# ProDocument_PWRTool_500_2024-05-11.net
KiCad netlist of a schematic drawn in EasyEDA Pro
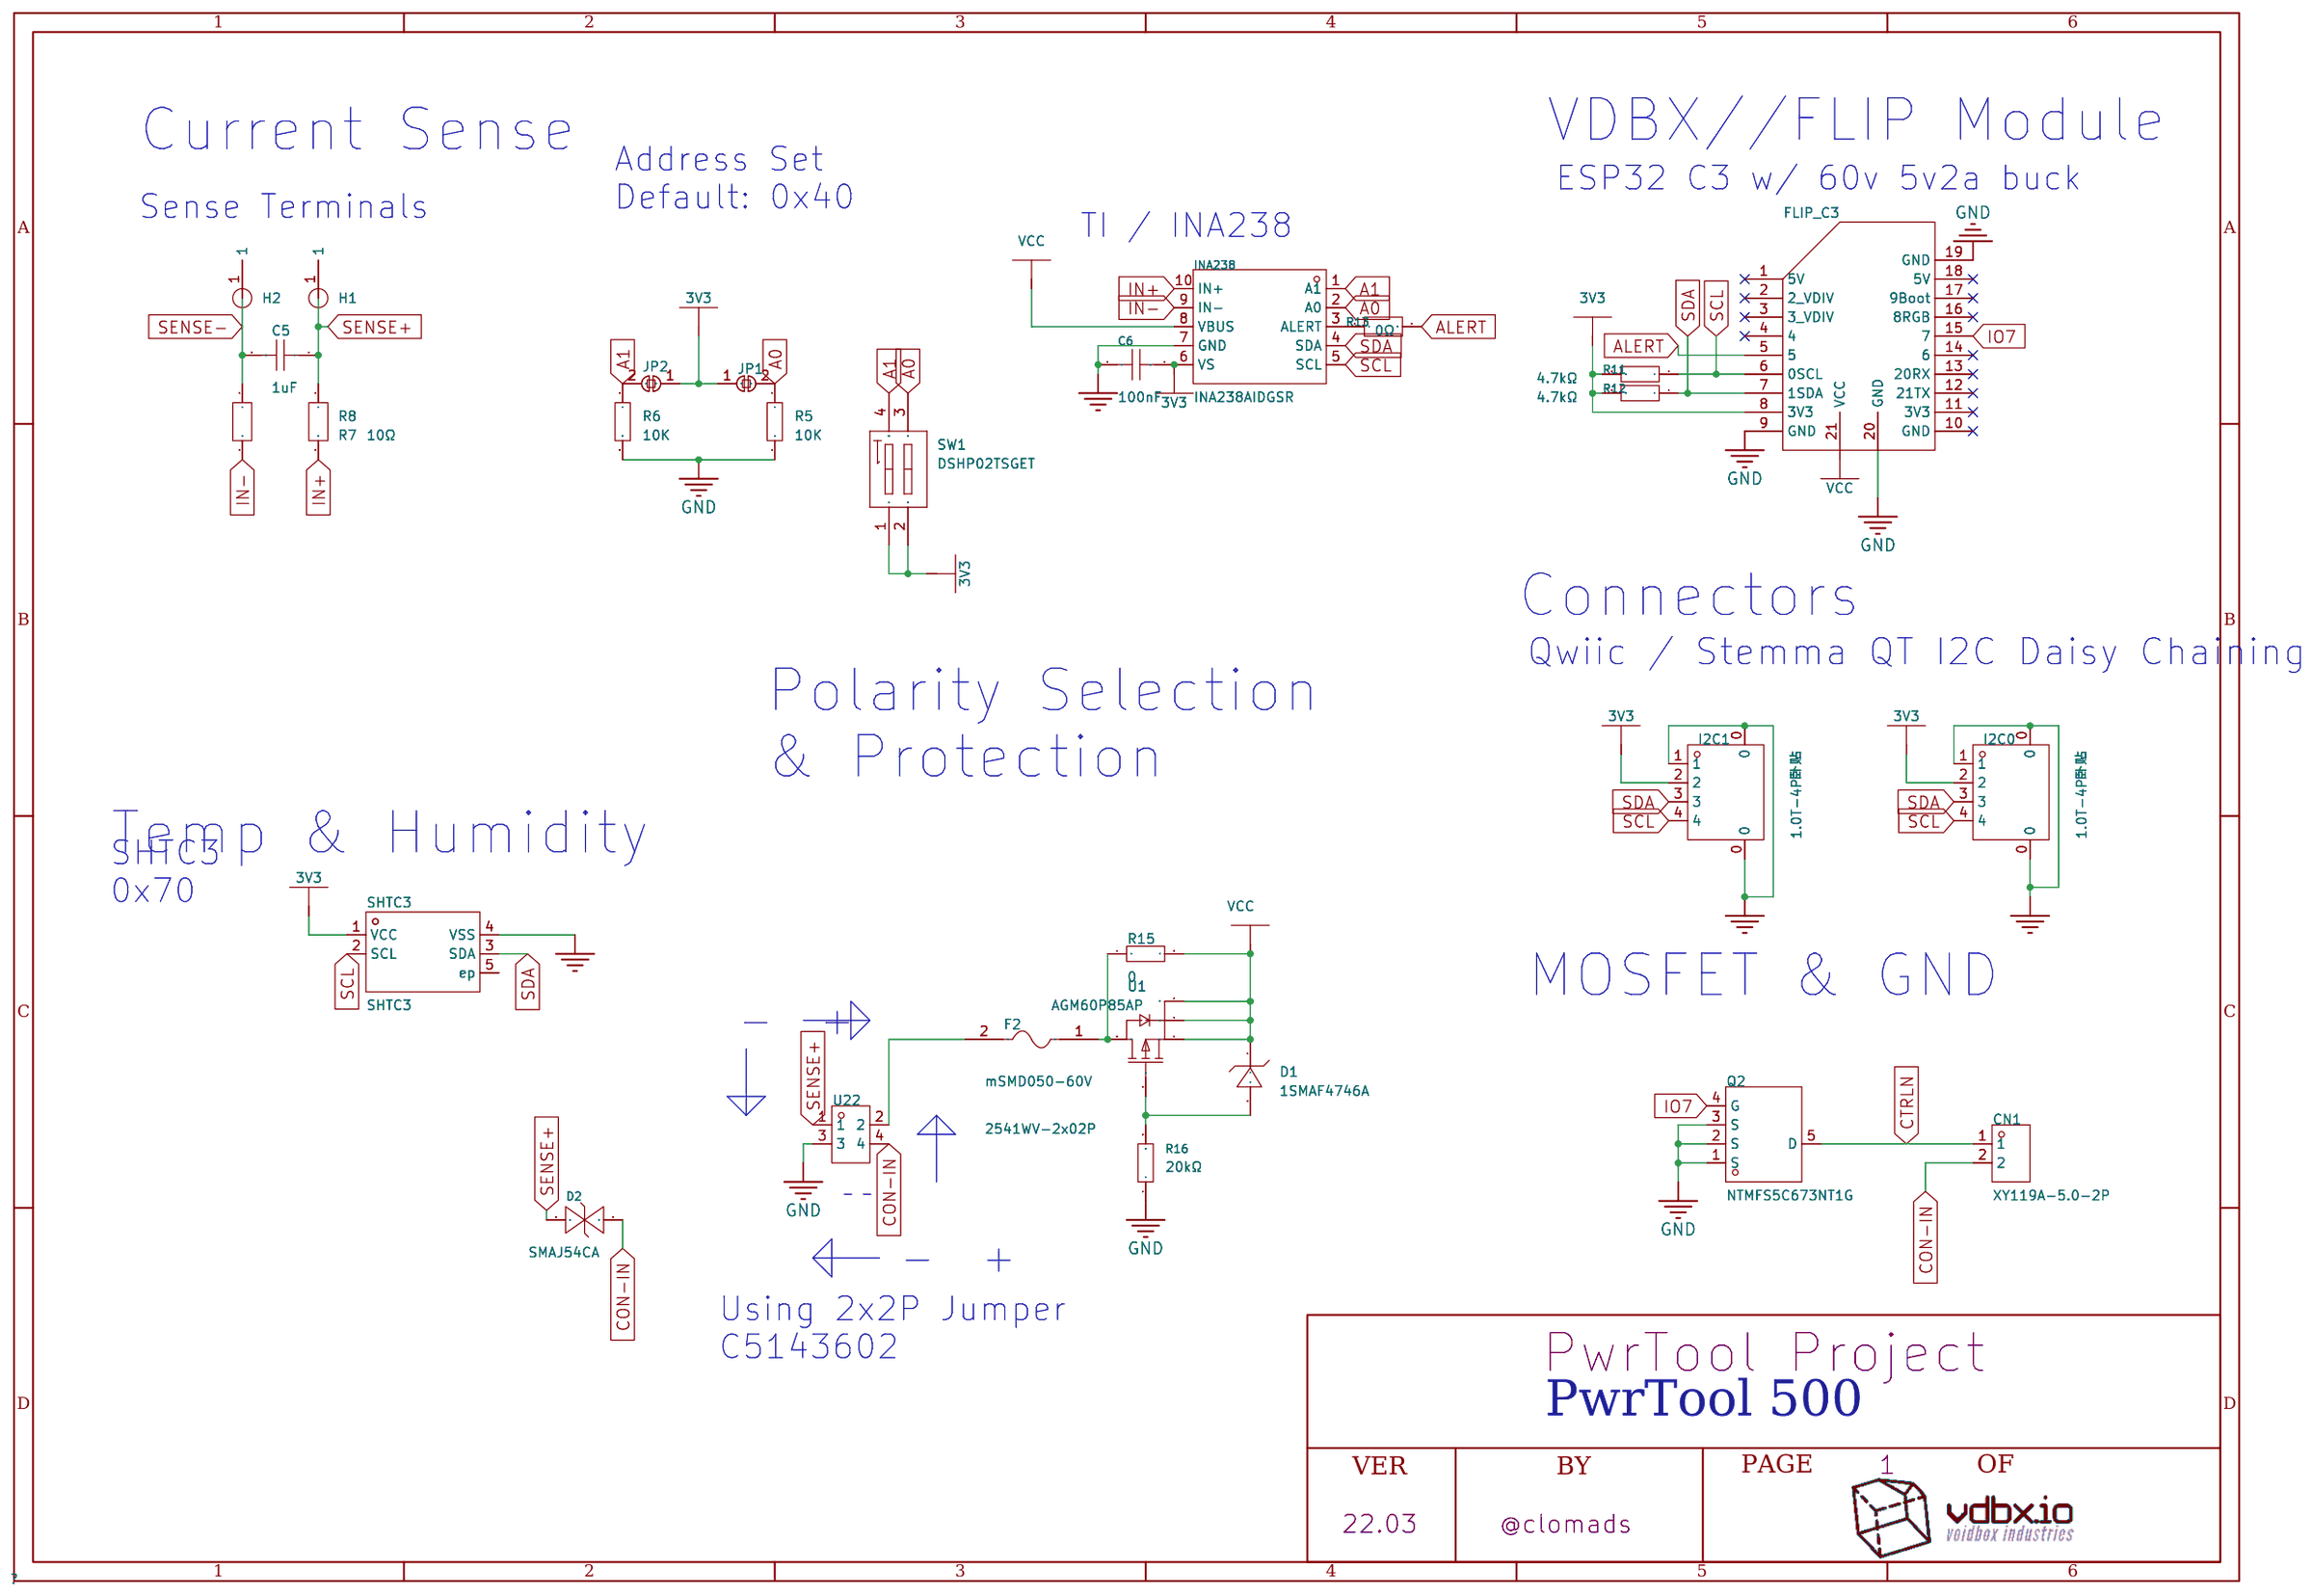
[diagram p0: schematic sheet]

(export (version "E")
  (design (tool "Eeschema 10.0.6"))
  (components
    (comp (ref "C5")
      (value "1uF")
      (footprint "easyedapro:C1206")
      (fields
        (field (name "Manufacturer Part") "TCC1206X7R105K101HT")
        (field (name "Manufacturer") "CCTC(三环)")
      )
      (libsource (lib "easyedapro") (part "TCC1206X7R105K101HT"))
    )
    (comp (ref "C6")
      (value "100nF")
      (footprint "easyedapro:C0402")
      (fields
        (field (name "Manufacturer Part") "CC0402JRX7R6BB104")
        (field (name "Manufacturer") "YAGEO(国巨)")
      )
      (libsource (lib "easyedapro") (part "CC0402JRX7R6BB104"))
    )
    (comp (ref "CN1")
      (value "XY119A-5.0-2P")
      (footprint "easyedapro:CONN-TH_XY119A-5.0-2P")
      (fields (field (name "Manufacturer") "XINLAIYA(新莱亚)"))
      (libsource (lib "easyedapro") (part "XY119A-5.0-2P"))
    )
    (comp (ref "D1")
      (value "1SMAF4746A")
      (footprint "easyedapro:SMAF_L3.5-W2.6-LS4.7-RD")
      (fields (field (name "Manufacturer") "晶导微电子"))
      (libsource (lib "easyedapro") (part "1SMAF4746A"))
    )
    (comp (ref "D2")
      (value "SMAJ54CA")
      (footprint "easyedapro:SMA_L4.4-W2.6-LS5.0-BI")
      (fields (field (name "Manufacturer") "TWGMC(台湾迪嘉)"))
      (libsource (lib "easyedapro") (part "SMAJ54CA_C726801"))
    )
    (comp (ref "F2")
      (value "mSMD050-60V")
      (footprint "easyedapro:F1812")
      (description "Operating Voltage (Max):60V Hold Current:500mA Current Rating (Max):100A Trip Current:1A")
      (fields (field (name "Manufacturer") "台湾陆海"))
      (libsource (lib "easyedapro") (part "mSMD050-60V"))
    )
    (comp (ref "FLIP_C3")
      (value "~")
      (footprint "easyedapro:VDBX//FLIP")
      (description "2.54mm DIP header for VDBX//FLIP")
      (libsource (lib "easyedapro") (part "VDBX//FLIP"))
    )
    (comp (ref "H1")
      (value "M2.5x3")
      (footprint "easyedapro:HDMod_MountingHole:SMTSO2530CTJ")
      (libsource (lib "easyedapro") (part "Mechanical Mount Hole 3mm"))
    )
    (comp (ref "H2")
      (value "M2.5x3")
      (footprint "easyedapro:HDMod_MountingHole:SMTSO2530CTJ")
      (libsource (lib "easyedapro") (part "Mechanical Mount Hole 3mm"))
    )
    (comp (ref "I2C0")
      (value "1.0T-4P卧贴")
      (footprint "easyedapro:CONN-SMD_1.0T-4P")
      (fields (field (name "Manufacturer") "BOOMELE(博穆精密)"))
      (libsource (lib "easyedapro") (part "1.0T-4P_C145956"))
    )
    (comp (ref "I2C1")
      (value "1.0T-4P卧贴")
      (footprint "easyedapro:CONN-SMD_1.0T-4P")
      (fields (field (name "Manufacturer") "BOOMELE(博穆精密)"))
      (libsource (lib "easyedapro") (part "1.0T-4P_C145956"))
    )
    (comp (ref "INA238")
      (value "INA238AIDGSR")
      (footprint "easyedapro:VSSOP-10_L3.0-W3.0-P0.50-LS4.9-BL")
      (fields (field (name "Manufacturer") "TI(德州仪器)"))
      (libsource (lib "easyedapro") (part "INA238AIDGSR"))
    )
    (comp (ref "JP1")
      (value "Jumper_SolderJumper_2_Bridged")
      (footprint "easyedapro:JUMPER")
      (libsource (lib "easyedapro") (part "Jumper_SolderJumper_2_Bridged"))
    )
    (comp (ref "JP2")
      (value "Jumper_SolderJumper_2_Bridged")
      (footprint "easyedapro:JUMPER")
      (libsource (lib "easyedapro") (part "Jumper_SolderJumper_2_Bridged"))
    )
    (comp (ref "Q2")
      (value "NTMFS5C673NT1G")
      (footprint "easyedapro:DFN-5_L4.9-W5.9-P1.27-LS6.2-BL")
      (fields (field (name "Manufacturer") "onsemi(安森美)"))
      (libsource (lib "easyedapro") (part "NTMFS5C673NT1G"))
    )
    (comp (ref "R5") (value "10K") (footprint "easyedapro:R0402") (libsource (lib "easyedapro") (part "Res")))
    (comp (ref "R6") (value "10K") (footprint "easyedapro:R0402") (libsource (lib "easyedapro") (part "Res")))
    (comp (ref "R7")
      (value "10Ω")
      (footprint "easyedapro:R0603")
      (fields
        (field (name "Manufacturer Part") "CRCW060310R0FKEA")
        (field (name "Manufacturer") "VISHAY(威世)")
      )
      (libsource (lib "easyedapro") (part "CRCW060310R0FKEA"))
    )
    (comp (ref "R8")
      (value "10Ω")
      (footprint "easyedapro:R0603")
      (fields
        (field (name "Manufacturer Part") "CRCW060310R0FKEA")
        (field (name "Manufacturer") "VISHAY(威世)")
      )
      (libsource (lib "easyedapro") (part "CRCW060310R0FKEA"))
    )
    (comp (ref "R11")
      (value "4.7kΩ")
      (footprint "easyedapro:R0805")
      (fields
        (field (name "Manufacturer Part") "0805W8J0472T5E")
        (field (name "Manufacturer") "UNI-ROYAL(厚声)")
      )
      (libsource (lib "easyedapro") (part "0805W8J0472T5E"))
    )
    (comp (ref "R12")
      (value "4.7kΩ")
      (footprint "easyedapro:R0805")
      (fields
        (field (name "Manufacturer Part") "0805W8J0472T5E")
        (field (name "Manufacturer") "UNI-ROYAL(厚声)")
      )
      (libsource (lib "easyedapro") (part "0805W8J0472T5E"))
    )
    (comp (ref "R13")
      (value "0Ω")
      (footprint "easyedapro:R0402")
      (fields (field (name "Manufacturer Part") "SCR0402J0R") (field (name "Manufacturer") "VO(翔胜)"))
      (libsource (lib "easyedapro") (part "SCR0402J0R"))
    )
    (comp (ref "R15") (value "0") (footprint "easyedapro:R0603") (libsource (lib "easyedapro") (part "Res")))
    (comp (ref "R16")
      (value "20kΩ")
      (footprint "easyedapro:R0805")
      (fields
        (field (name "Manufacturer Part") "0805W8F2002T5E")
        (field (name "Manufacturer") "UNI-ROYAL(厚声)")
      )
      (libsource (lib "easyedapro") (part "0805W8F2002T5E"))
    )
    (comp (ref "SHTC3")
      (value "SHTC3")
      (footprint "easyedapro:SENSORM-SMD_4P-L2.0-W2.0-P1.00")
      (fields (field (name "Manufacturer") "Sensirion(瑞士盛思锐)"))
      (libsource (lib "easyedapro") (part "SHTC3"))
    )
    (comp (ref "SW1")
      (value "DSHP02TSGET")
      (footprint "easyedapro:SW-SMD_4P_DSHP02TSGET")
      (description "Type:平拨，Notch式 Circuit:SPST Number of Positions:2 Lead Pitch:1.27mm Color:Black")
      (fields (field (name "Manufacturer") "YE"))
      (libsource (lib "easyedapro") (part "DSHP02TSGET"))
    )
    (comp (ref "U1")
      (value "AGM60P85AP")
      (footprint "easyedapro:WDFN-5_L3.3-W3.3-P0.65-BL")
      (fields (field (name "Manufacturer") "AGM-Semi(芯控源)"))
      (libsource (lib "easyedapro") (part "AGM60P85AP"))
    )
    (comp (ref "U22")
      (value "2541WV-2x02P")
      (footprint "easyedapro:HDR-TH_4P-P2.54-V-M-R2-C2-S2.54")
      (fields (field (name "Manufacturer") "HanElectricity(瀚源)"))
      (libsource (lib "easyedapro") (part "2541WV-2X02P"))
    )
  )
  (nets
    (net (code "1") (name "3V3") (class "Default")
      (node (ref "C6") (pin "2") (pinfunction "2_2") (pintype "input"))
      (node (ref "FLIP_C3") (pin "8") (pinfunction "3V3_8") (pintype "input"))
      (node (ref "I2C0") (pin "2") (pinfunction "2_2") (pintype "input"))
      (node (ref "I2C1") (pin "2") (pinfunction "2_2") (pintype "input"))
      (node (ref "INA238") (pin "6") (pinfunction "VS_6") (pintype "input"))
      (node (ref "JP1") (pin "1") (pinfunction "A_1") (pintype "input"))
      (node (ref "JP2") (pin "1") (pinfunction "A_1") (pintype "input"))
      (node (ref "R11") (pin "2") (pinfunction "2_2") (pintype "input"))
      (node (ref "R12") (pin "2") (pinfunction "2_2") (pintype "input"))
      (node (ref "SHTC3") (pin "1") (pinfunction "VCC_1") (pintype "input"))
      (node (ref "SW1") (pin "1") (pinfunction "A1_1") (pintype "input"))
      (node (ref "SW1") (pin "2") (pinfunction "A2_2") (pintype "input"))
    )
    (net (code "2") (name "A0") (class "Default")
      (node (ref "INA238") (pin "2") (pinfunction "A0_2") (pintype "input"))
      (node (ref "JP1") (pin "2") (pinfunction "B_2") (pintype "input"))
      (node (ref "R5") (pin "1") (pinfunction "1_1") (pintype "input"))
      (node (ref "SW1") (pin "3") (pinfunction "B2_3") (pintype "input"))
    )
    (net (code "3") (name "A1") (class "Default")
      (node (ref "INA238") (pin "1") (pinfunction "A1_1") (pintype "input"))
      (node (ref "JP2") (pin "2") (pinfunction "B_2") (pintype "input"))
      (node (ref "R6") (pin "1") (pinfunction "1_1") (pintype "input"))
      (node (ref "SW1") (pin "4") (pinfunction "B1_4") (pintype "input"))
    )
    (net (code "4") (name "ALERT") (class "Default")
      (node (ref "FLIP_C3") (pin "5") (pinfunction "5_5") (pintype "input"))
      (node (ref "R13") (pin "2") (pinfunction "2_2") (pintype "input"))
    )
    (net (code "5") (name "CON-IN") (class "Default")
      (node (ref "CN1") (pin "2") (pinfunction "2_2") (pintype "input"))
      (node (ref "D2") (pin "1") (pinfunction "1_1") (pintype "input"))
      (node (ref "U22") (pin "4") (pinfunction "4_4") (pintype "input"))
    )
    (net (code "6") (name "CTRLN") (class "Default")
      (node (ref "CN1") (pin "1") (pinfunction "1_1") (pintype "input"))
      (node (ref "Q2") (pin "5") (pinfunction "D_5") (pintype "input"))
    )
    (net (code "7") (name "GND") (class "Default")
      (node (ref "C6") (pin "1") (pinfunction "1_1") (pintype "input"))
      (node (ref "FLIP_C3") (pin "19") (pinfunction "GND_19") (pintype "input"))
      (node (ref "FLIP_C3") (pin "20") (pinfunction "GND_20") (pintype "input"))
      (node (ref "FLIP_C3") (pin "9") (pinfunction "GND_9") (pintype "input"))
      (node (ref "I2C0") (pin "0") (pinfunction "0_0") (pintype "input"))
      (node (ref "I2C0") (pin "1") (pinfunction "1_1") (pintype "input"))
      (node (ref "I2C1") (pin "0") (pinfunction "0_0") (pintype "input"))
      (node (ref "I2C1") (pin "1") (pinfunction "1_1") (pintype "input"))
      (node (ref "INA238") (pin "7") (pinfunction "GND_7") (pintype "input"))
      (node (ref "Q2") (pin "1") (pinfunction "S_1") (pintype "input"))
      (node (ref "Q2") (pin "2") (pinfunction "S_2") (pintype "input"))
      (node (ref "Q2") (pin "3") (pinfunction "S_3") (pintype "input"))
      (node (ref "R16") (pin "1") (pinfunction "1_1") (pintype "input"))
      (node (ref "R5") (pin "2") (pinfunction "2_2") (pintype "input"))
      (node (ref "R6") (pin "2") (pinfunction "2_2") (pintype "input"))
      (node (ref "SHTC3") (pin "4") (pinfunction "VSS_4") (pintype "input"))
      (node (ref "U22") (pin "3") (pinfunction "3_3") (pintype "input"))
    )
    (net (code "8") (name "IN+") (class "Default")
      (node (ref "INA238") (pin "10") (pinfunction "IN+_10") (pintype "input"))
      (node (ref "R7") (pin "2") (pinfunction "2_2") (pintype "input"))
    )
    (net (code "9") (name "IN-") (class "Default")
      (node (ref "INA238") (pin "9") (pinfunction "IN-_9") (pintype "input"))
      (node (ref "R8") (pin "2") (pinfunction "2_2") (pintype "input"))
    )
    (net (code "10") (name "IO7") (class "Default")
      (node (ref "FLIP_C3") (pin "15") (pinfunction "7_15") (pintype "input"))
      (node (ref "Q2") (pin "4") (pinfunction "G_4") (pintype "input"))
    )
    (net (code "11") (name "Net-(D1-A)") (class "Default")
      (node (ref "D1") (pin "2") (pinfunction "A_2") (pintype "input"))
      (node (ref "R16") (pin "2") (pinfunction "2_2") (pintype "input"))
      (node (ref "U1") (pin "4") (pinfunction "G_4") (pintype "unspecified"))
    )
    (net (code "12") (name "Net-(F2-Pad2)") (class "Default")
      (node (ref "F2") (pin "2") (pinfunction "2_2") (pintype "input"))
      (node (ref "U22") (pin "2") (pinfunction "2_2") (pintype "input"))
    )
    (net (code "13") (name "Net-(INA238-ALERT)") (class "Default")
      (node (ref "INA238") (pin "3") (pinfunction "ALERT_3") (pintype "input"))
      (node (ref "R13") (pin "1") (pinfunction "1_1") (pintype "input"))
    )
    (net (code "14") (name "Net-(U1-D)") (class "Default")
      (node (ref "F2") (pin "1") (pinfunction "1_1") (pintype "input"))
      (node (ref "R15") (pin "1") (pinfunction "1_1") (pintype "input"))
      (node (ref "U1") (pin "5") (pinfunction "D_5") (pintype "unspecified"))
    )
    (net (code "15") (name "SCL") (class "Default")
      (node (ref "FLIP_C3") (pin "6") (pinfunction "0SCL_6") (pintype "input"))
      (node (ref "I2C0") (pin "4") (pinfunction "4_4") (pintype "input"))
      (node (ref "I2C1") (pin "4") (pinfunction "4_4") (pintype "input"))
      (node (ref "INA238") (pin "5") (pinfunction "SCL_5") (pintype "input"))
      (node (ref "R11") (pin "1") (pinfunction "1_1") (pintype "input"))
      (node (ref "SHTC3") (pin "2") (pinfunction "SCL_2") (pintype "input"))
    )
    (net (code "16") (name "SDA") (class "Default")
      (node (ref "FLIP_C3") (pin "7") (pinfunction "1SDA_7") (pintype "input"))
      (node (ref "I2C0") (pin "3") (pinfunction "3_3") (pintype "input"))
      (node (ref "I2C1") (pin "3") (pinfunction "3_3") (pintype "input"))
      (node (ref "INA238") (pin "4") (pinfunction "SDA_4") (pintype "input"))
      (node (ref "R12") (pin "1") (pinfunction "1_1") (pintype "input"))
      (node (ref "SHTC3") (pin "3") (pinfunction "SDA_3") (pintype "input"))
    )
    (net (code "17") (name "SENSE+") (class "Default")
      (node (ref "C5") (pin "1") (pinfunction "1_1") (pintype "input"))
      (node (ref "D2") (pin "2") (pinfunction "2_2") (pintype "input"))
      (node (ref "H1") (pin "1") (pinfunction "1_1") (pintype "input"))
      (node (ref "R7") (pin "1") (pinfunction "1_1") (pintype "input"))
      (node (ref "U22") (pin "1") (pinfunction "1_1") (pintype "input"))
    )
    (net (code "18") (name "SENSE-") (class "Default")
      (node (ref "C5") (pin "2") (pinfunction "2_2") (pintype "input"))
      (node (ref "H2") (pin "1") (pinfunction "1_1") (pintype "input"))
      (node (ref "R8") (pin "1") (pinfunction "1_1") (pintype "input"))
    )
    (net (code "19") (name "VCC") (class "Default")
      (node (ref "D1") (pin "1") (pinfunction "K_1") (pintype "input"))
      (node (ref "FLIP_C3") (pin "21") (pinfunction "VCC_21") (pintype "input"))
      (node (ref "INA238") (pin "8") (pinfunction "VBUS_8") (pintype "input"))
      (node (ref "R15") (pin "2") (pinfunction "2_2") (pintype "input"))
      (node (ref "U1") (pin "1") (pinfunction "S_1") (pintype "unspecified"))
      (node (ref "U1") (pin "2") (pinfunction "S_2") (pintype "unspecified"))
      (node (ref "U1") (pin "3") (pinfunction "S_3") (pintype "unspecified"))
    )
    (net (code "20") (name "unconnected-(FLIP_C3-2_VDIV-Pad2)") (class "Default")
      (node (ref "FLIP_C3") (pin "2") (pinfunction "2_VDIV_2") (pintype "input+no_connect"))
    )
    (net (code "21") (name "unconnected-(FLIP_C3-3V3-Pad11)") (class "Default")
      (node (ref "FLIP_C3") (pin "11") (pinfunction "3V3_11") (pintype "input+no_connect"))
    )
    (net (code "22") (name "unconnected-(FLIP_C3-3_VDIV-Pad3)") (class "Default")
      (node (ref "FLIP_C3") (pin "3") (pinfunction "3_VDIV_3") (pintype "input+no_connect"))
    )
    (net (code "23") (name "unconnected-(FLIP_C3-5V-Pad1)") (class "Default")
      (node (ref "FLIP_C3") (pin "1") (pinfunction "5V_1") (pintype "input+no_connect"))
    )
    (net (code "24") (name "unconnected-(FLIP_C3-5V-Pad18)") (class "Default")
      (node (ref "FLIP_C3") (pin "18") (pinfunction "5V_18") (pintype "input+no_connect"))
    )
    (net (code "25") (name "unconnected-(FLIP_C3-6-Pad14)") (class "Default")
      (node (ref "FLIP_C3") (pin "14") (pinfunction "6_14") (pintype "input+no_connect"))
    )
    (net (code "26") (name "unconnected-(FLIP_C3-8RGB-Pad16)") (class "Default")
      (node (ref "FLIP_C3") (pin "16") (pinfunction "8RGB_16") (pintype "input+no_connect"))
    )
    (net (code "27") (name "unconnected-(FLIP_C3-9Boot-Pad17)") (class "Default")
      (node (ref "FLIP_C3") (pin "17") (pinfunction "9Boot_17") (pintype "input+no_connect"))
    )
    (net (code "28") (name "unconnected-(FLIP_C3-20RX-Pad13)") (class "Default")
      (node (ref "FLIP_C3") (pin "13") (pinfunction "20RX_13") (pintype "input+no_connect"))
    )
    (net (code "29") (name "unconnected-(FLIP_C3-21TX-Pad12)") (class "Default")
      (node (ref "FLIP_C3") (pin "12") (pinfunction "21TX_12") (pintype "input+no_connect"))
    )
    (net (code "30") (name "unconnected-(FLIP_C3-GND-Pad10)") (class "Default")
      (node (ref "FLIP_C3") (pin "10") (pinfunction "GND_10") (pintype "input+no_connect"))
    )
    (net (code "31") (name "unconnected-(FLIP_C3-Pad4)") (class "Default")
      (node (ref "FLIP_C3") (pin "4") (pinfunction "4_4") (pintype "input+no_connect"))
    )
    (net (code "32") (name "unconnected-(SHTC3-ep-Pad5)") (class "Default")
      (node (ref "SHTC3") (pin "5") (pinfunction "ep_5") (pintype "input"))
    )
  )
)
